# switches.net
KiCad netlist of a schematic drawn in EAGLE
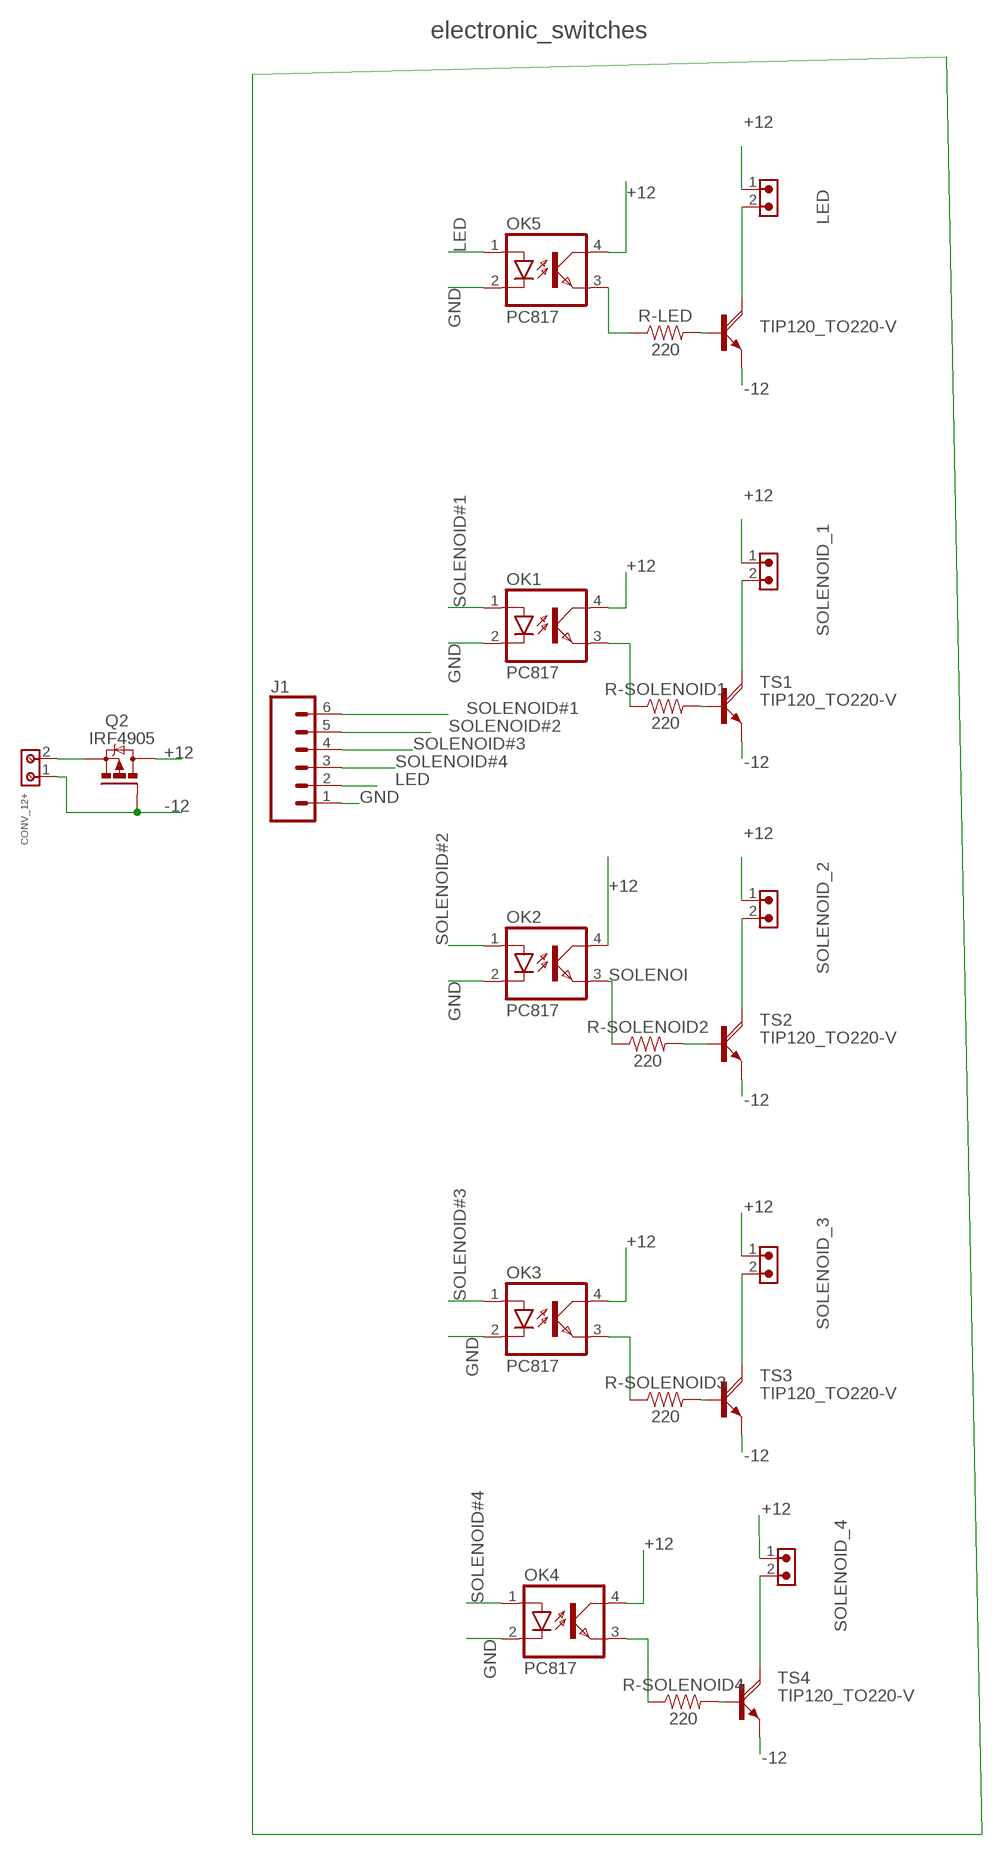
[diagram p0: schematic, sheet 1]

(export (version "E")
  (design (tool "Eeschema 10.0.6"))
  (components
    (comp (ref "CONV_12+")
      (value "691213500002")
      (footprint "eagle-import:691213500002")
      (libsource (lib "eagle-import") (part "691213500002"))
    )
    (comp (ref "J1")
      (value "CONN_06FEMALE_LOCK")
      (footprint "eagle-import:1X06_FEMALE_LOCK.010")
      (libsource (lib "eagle-import") (part "CONN_06FEMALE_LOCK"))
    )
    (comp (ref "LED")
      (value "691305540002")
      (footprint "eagle-import:691305540002")
      (libsource (lib "eagle-import") (part "691305540002"))
    )
    (comp (ref "LED3")
      (value "TIP120_TO220-V")
      (footprint "eagle-import:TO220V")
      (libsource (lib "eagle-import") (part "TIP120_TO220-V"))
    )
    (comp (ref "OK1")
      (value "PC817")
      (footprint "eagle-import:DIL04")
      (fields (field (name "MPN") "PC817X4J000F"))
      (libsource (lib "eagle-import") (part "PC817"))
    )
    (comp (ref "OK2")
      (value "PC817")
      (footprint "eagle-import:DIL04")
      (fields (field (name "MPN") "PC817X4J000F"))
      (libsource (lib "eagle-import") (part "PC817"))
    )
    (comp (ref "OK3")
      (value "PC817")
      (footprint "eagle-import:DIL04")
      (fields (field (name "MPN") "PC817X4J000F"))
      (libsource (lib "eagle-import") (part "PC817"))
    )
    (comp (ref "OK4")
      (value "PC817")
      (footprint "eagle-import:DIL04")
      (fields (field (name "MPN") "PC817X4J000F"))
      (libsource (lib "eagle-import") (part "PC817"))
    )
    (comp (ref "OK5")
      (value "PC817")
      (footprint "eagle-import:DIL04")
      (fields (field (name "MPN") "PC817X4J000F"))
      (libsource (lib "eagle-import") (part "PC817"))
    )
    (comp (ref "Q2")
      (value "IRF4905")
      (footprint "eagle-import:TO220BH")
      (libsource (lib "eagle-import") (part "IRF4905"))
    )
    (comp (ref "R-LED")
      (value "220")
      (footprint "eagle-import:AXIAL-0.3")
      (libsource (lib "eagle-import") (part "10MOHM-HORIZ-1/4W-5%"))
    )
    (comp (ref "R-SOLENOID1")
      (value "220")
      (footprint "eagle-import:AXIAL-0.3")
      (libsource (lib "eagle-import") (part "10MOHM-HORIZ-1/4W-5%"))
    )
    (comp (ref "R-SOLENOID2")
      (value "220")
      (footprint "eagle-import:AXIAL-0.3")
      (libsource (lib "eagle-import") (part "10MOHM-HORIZ-1/4W-5%"))
    )
    (comp (ref "R-SOLENOID3")
      (value "220")
      (footprint "eagle-import:AXIAL-0.3")
      (libsource (lib "eagle-import") (part "10MOHM-HORIZ-1/4W-5%"))
    )
    (comp (ref "R-SOLENOID4")
      (value "220")
      (footprint "eagle-import:AXIAL-0.3")
      (libsource (lib "eagle-import") (part "10MOHM-HORIZ-1/4W-5%"))
    )
    (comp (ref "SOLENOID_1")
      (value "691305540002")
      (footprint "eagle-import:691305540002")
      (libsource (lib "eagle-import") (part "691305540002"))
    )
    (comp (ref "SOLENOID_2")
      (value "691305540002")
      (footprint "eagle-import:691305540002")
      (libsource (lib "eagle-import") (part "691305540002"))
    )
    (comp (ref "SOLENOID_3")
      (value "691305540002")
      (footprint "eagle-import:691305540002")
      (libsource (lib "eagle-import") (part "691305540002"))
    )
    (comp (ref "SOLENOID_4")
      (value "691305540002")
      (footprint "eagle-import:691305540002")
      (libsource (lib "eagle-import") (part "691305540002"))
    )
    (comp (ref "TS1")
      (value "TIP120_TO220-V")
      (footprint "eagle-import:TO220V")
      (libsource (lib "eagle-import") (part "TIP120_TO220-V"))
    )
    (comp (ref "TS2")
      (value "TIP120_TO220-V")
      (footprint "eagle-import:TO220V")
      (libsource (lib "eagle-import") (part "TIP120_TO220-V"))
    )
    (comp (ref "TS3")
      (value "TIP120_TO220-V")
      (footprint "eagle-import:TO220V")
      (libsource (lib "eagle-import") (part "TIP120_TO220-V"))
    )
    (comp (ref "TS4")
      (value "TIP120_TO220-V")
      (footprint "eagle-import:TO220V")
      (libsource (lib "eagle-import") (part "TIP120_TO220-V"))
    )
  )
  (nets
    (net (code "1") (name "/+12") (class "Default")
      (node (ref "LED") (pin "1") (pinfunction "1_1") (pintype "passive"))
      (node (ref "OK1") (pin "4") (pinfunction "COL_4") (pintype "passive"))
      (node (ref "OK2") (pin "4") (pinfunction "COL_4") (pintype "passive"))
      (node (ref "OK3") (pin "4") (pinfunction "COL_4") (pintype "passive"))
      (node (ref "OK4") (pin "4") (pinfunction "COL_4") (pintype "passive"))
      (node (ref "OK5") (pin "4") (pinfunction "COL_4") (pintype "passive"))
      (node (ref "Q2") (pin "D") (pinfunction "D_D") (pintype "passive"))
      (node (ref "SOLENOID_1") (pin "1") (pinfunction "1_1") (pintype "passive"))
      (node (ref "SOLENOID_2") (pin "1") (pinfunction "1_1") (pintype "passive"))
      (node (ref "SOLENOID_3") (pin "1") (pinfunction "1_1") (pintype "passive"))
      (node (ref "SOLENOID_4") (pin "1") (pinfunction "1_1") (pintype "passive"))
    )
    (net (code "2") (name "/-12") (class "Default")
      (node (ref "CONV_12+") (pin "1") (pinfunction "1_1") (pintype "passive"))
      (node (ref "LED3") (pin "3") (pinfunction "E_3") (pintype "passive"))
      (node (ref "Q2") (pin "G") (pinfunction "G_G") (pintype "passive"))
      (node (ref "TS1") (pin "3") (pinfunction "E_3") (pintype "passive"))
      (node (ref "TS2") (pin "3") (pinfunction "E_3") (pintype "passive"))
      (node (ref "TS3") (pin "3") (pinfunction "E_3") (pintype "passive"))
      (node (ref "TS4") (pin "3") (pinfunction "E_3") (pintype "passive"))
    )
    (net (code "3") (name "/GND") (class "Default")
      (node (ref "J1") (pin "1") (pinfunction "1_1") (pintype "passive"))
      (node (ref "OK1") (pin "2") (pinfunction "C_2") (pintype "passive"))
      (node (ref "OK2") (pin "2") (pinfunction "C_2") (pintype "passive"))
      (node (ref "OK3") (pin "2") (pinfunction "C_2") (pintype "passive"))
      (node (ref "OK4") (pin "2") (pinfunction "C_2") (pintype "passive"))
      (node (ref "OK5") (pin "2") (pinfunction "C_2") (pintype "passive"))
    )
    (net (code "4") (name "/LED") (class "Default")
      (node (ref "J1") (pin "2") (pinfunction "2_2") (pintype "passive"))
      (node (ref "OK5") (pin "1") (pinfunction "A_1") (pintype "passive"))
    )
    (net (code "5") (name "/SOLENOI") (class "Default")
      (node (ref "OK2") (pin "3") (pinfunction "EMIT_3") (pintype "passive"))
      (node (ref "R-SOLENOID2") (pin "P$1") (pinfunction "1_P$1") (pintype "passive"))
    )
    (net (code "6") (name "/SOLENOID#1") (class "Default")
      (node (ref "J1") (pin "6") (pinfunction "6_6") (pintype "passive"))
      (node (ref "OK1") (pin "1") (pinfunction "A_1") (pintype "passive"))
    )
    (net (code "7") (name "/SOLENOID#2") (class "Default")
      (node (ref "J1") (pin "5") (pinfunction "5_5") (pintype "passive"))
      (node (ref "OK2") (pin "1") (pinfunction "A_1") (pintype "passive"))
    )
    (net (code "8") (name "/SOLENOID#3") (class "Default")
      (node (ref "J1") (pin "4") (pinfunction "4_4") (pintype "passive"))
      (node (ref "OK3") (pin "1") (pinfunction "A_1") (pintype "passive"))
    )
    (net (code "9") (name "/SOLENOID#4") (class "Default")
      (node (ref "J1") (pin "3") (pinfunction "3_3") (pintype "passive"))
      (node (ref "OK4") (pin "1") (pinfunction "A_1") (pintype "passive"))
    )
    (net (code "10") (name "Net-(CONV_12+-Pad2)") (class "Default")
      (node (ref "CONV_12+") (pin "2") (pinfunction "2_2") (pintype "passive"))
      (node (ref "Q2") (pin "S") (pinfunction "S_S") (pintype "passive"))
    )
    (net (code "11") (name "Net-(LED3-B)") (class "Default")
      (node (ref "LED3") (pin "1") (pinfunction "B_1") (pintype "passive"))
      (node (ref "R-LED") (pin "P$2") (pinfunction "2_P$2") (pintype "passive"))
    )
    (net (code "12") (name "Net-(LED3-C)") (class "Default")
      (node (ref "LED") (pin "2") (pinfunction "2_2") (pintype "passive"))
      (node (ref "LED3") (pin "2") (pinfunction "C_2") (pintype "passive"))
    )
    (net (code "13") (name "Net-(OK1-EMIT)") (class "Default")
      (node (ref "OK1") (pin "3") (pinfunction "EMIT_3") (pintype "passive"))
      (node (ref "R-SOLENOID1") (pin "P$1") (pinfunction "1_P$1") (pintype "passive"))
    )
    (net (code "14") (name "Net-(OK3-EMIT)") (class "Default")
      (node (ref "OK3") (pin "3") (pinfunction "EMIT_3") (pintype "passive"))
      (node (ref "R-SOLENOID3") (pin "P$1") (pinfunction "1_P$1") (pintype "passive"))
    )
    (net (code "15") (name "Net-(OK4-EMIT)") (class "Default")
      (node (ref "OK4") (pin "3") (pinfunction "EMIT_3") (pintype "passive"))
      (node (ref "R-SOLENOID4") (pin "P$1") (pinfunction "1_P$1") (pintype "passive"))
    )
    (net (code "16") (name "Net-(OK5-EMIT)") (class "Default")
      (node (ref "OK5") (pin "3") (pinfunction "EMIT_3") (pintype "passive"))
      (node (ref "R-LED") (pin "P$1") (pinfunction "1_P$1") (pintype "passive"))
    )
    (net (code "17") (name "Net-(R-SOLENOID1-2)") (class "Default")
      (node (ref "R-SOLENOID1") (pin "P$2") (pinfunction "2_P$2") (pintype "passive"))
      (node (ref "TS1") (pin "1") (pinfunction "B_1") (pintype "passive"))
    )
    (net (code "18") (name "Net-(R-SOLENOID2-2)") (class "Default")
      (node (ref "R-SOLENOID2") (pin "P$2") (pinfunction "2_P$2") (pintype "passive"))
      (node (ref "TS2") (pin "1") (pinfunction "B_1") (pintype "passive"))
    )
    (net (code "19") (name "Net-(R-SOLENOID3-2)") (class "Default")
      (node (ref "R-SOLENOID3") (pin "P$2") (pinfunction "2_P$2") (pintype "passive"))
      (node (ref "TS3") (pin "1") (pinfunction "B_1") (pintype "passive"))
    )
    (net (code "20") (name "Net-(R-SOLENOID4-2)") (class "Default")
      (node (ref "R-SOLENOID4") (pin "P$2") (pinfunction "2_P$2") (pintype "passive"))
      (node (ref "TS4") (pin "1") (pinfunction "B_1") (pintype "passive"))
    )
    (net (code "21") (name "Net-(TS1-C)") (class "Default")
      (node (ref "SOLENOID_1") (pin "2") (pinfunction "2_2") (pintype "passive"))
      (node (ref "TS1") (pin "2") (pinfunction "C_2") (pintype "passive"))
    )
    (net (code "22") (name "Net-(TS2-C)") (class "Default")
      (node (ref "SOLENOID_2") (pin "2") (pinfunction "2_2") (pintype "passive"))
      (node (ref "TS2") (pin "2") (pinfunction "C_2") (pintype "passive"))
    )
    (net (code "23") (name "Net-(TS3-C)") (class "Default")
      (node (ref "SOLENOID_3") (pin "2") (pinfunction "2_2") (pintype "passive"))
      (node (ref "TS3") (pin "2") (pinfunction "C_2") (pintype "passive"))
    )
    (net (code "24") (name "Net-(TS4-C)") (class "Default")
      (node (ref "SOLENOID_4") (pin "2") (pinfunction "2_2") (pintype "passive"))
      (node (ref "TS4") (pin "2") (pinfunction "C_2") (pintype "passive"))
    )
  )
)
